# AUX_Sensor_Board.net
KiCad netlist of a schematic drawn in Altium Designer
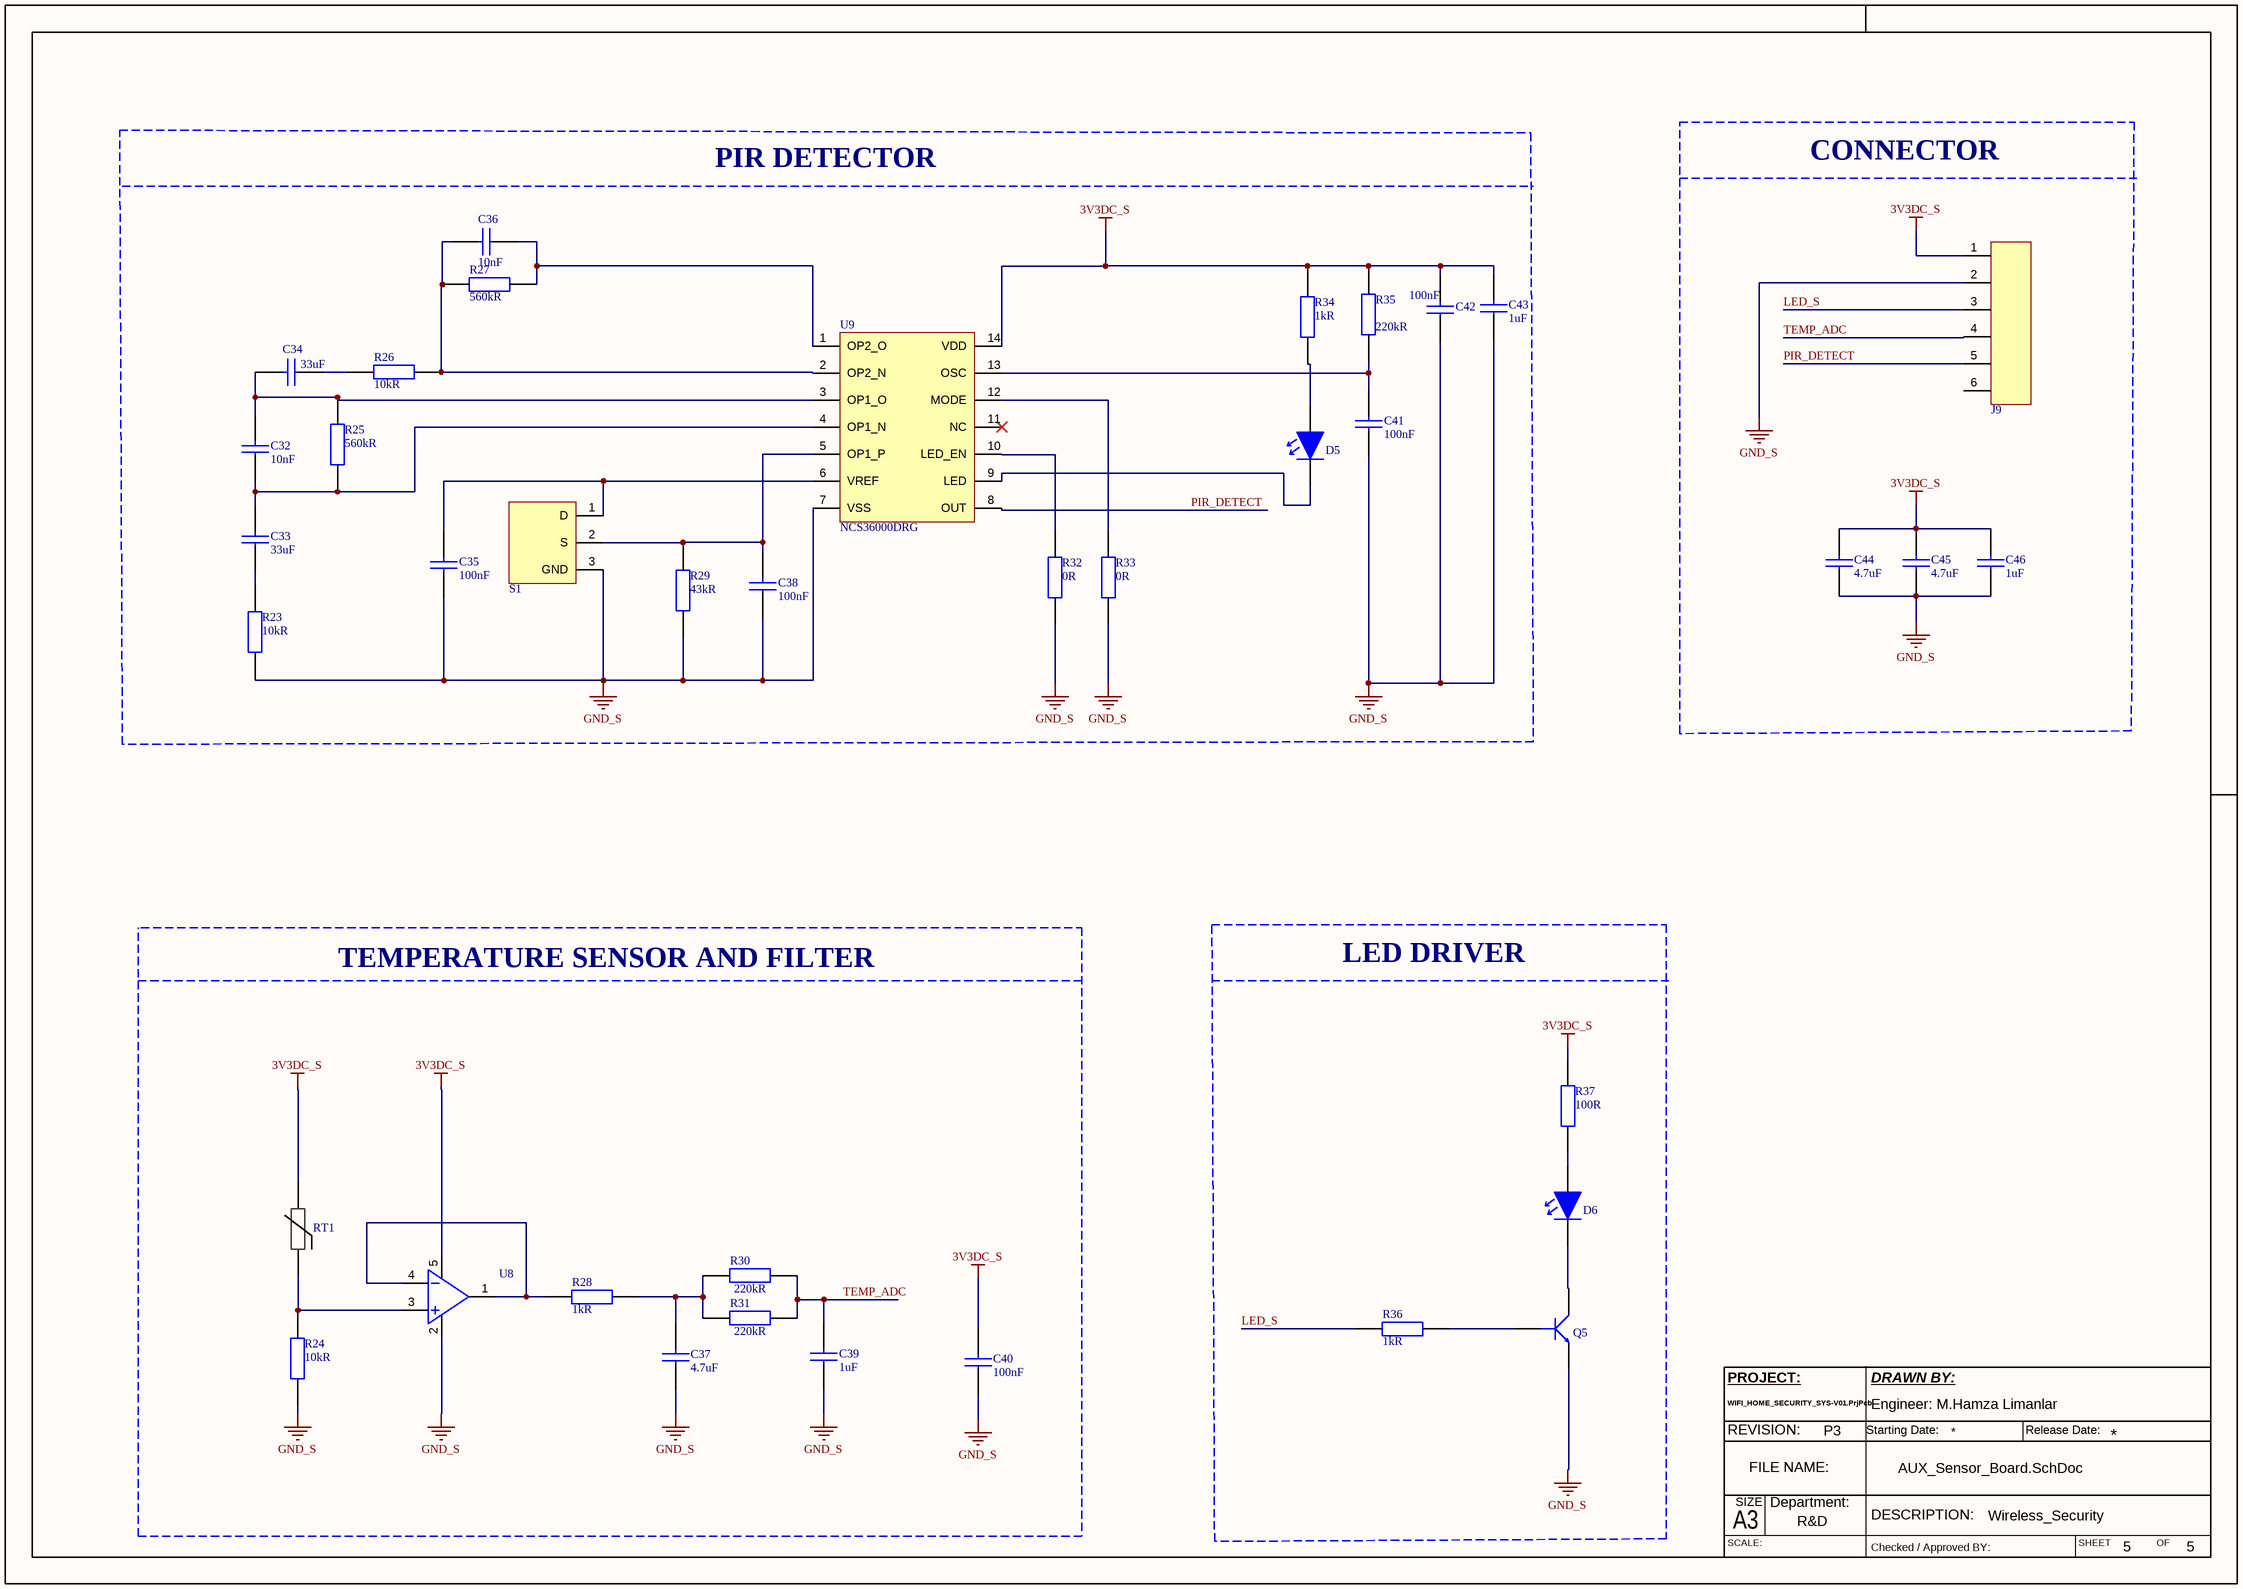
[diagram p0: AUX_Sensor_Board.SchDoc]

(export (version "E")
  (design (tool "Eeschema 10.0.6"))
  (components
    (comp (ref "C32")
      (value "0603B103K160CT")
      (footprint "CAP_0603")
      (description "CAP CER 10nF %10 0603")
      (fields
        (field (name "MANUFACTURER") "Walsin Technologies")
        (field (name "TOLERANCE") "10%")
        (field (name "CAPACITANCE") "10nF")
        (field (name "DESIGNED BY") "M.HamzaLimanlar")
      )
      (libsource (lib "HOME_SECURITY_SYSTEM_PROJECT_LIB") (part "CAP CER 10nF 0603"))
    )
    (comp (ref "C33")
      (value "C3216X5R1E336M160AC")
      (footprint "CAP_1206")
      (description "CAP CER 33uF %20 1206 SMD")
      (fields
        (field (name "MANUFACTURER") "TDK")
        (field (name "TOLERANCE") "20%")
        (field (name "CAPACITANCE") "33uF")
        (field (name "DESIGNED BY") "M.HamzaLimanlar")
      )
      (libsource (lib "HOME_SECURITY_SYSTEM_PROJECT_LIB") (part "CAP CER 33uF 1206"))
    )
    (comp (ref "C34")
      (value "C3216X5R1E336M160AC")
      (footprint "CAP_1206")
      (description "CAP CER 33uF %20 1206 SMD")
      (fields
        (field (name "MANUFACTURER") "TDK")
        (field (name "TOLERANCE") "20%")
        (field (name "CAPACITANCE") "33uF")
        (field (name "DESIGNED BY") "M.HamzaLimanlar")
      )
      (libsource (lib "HOME_SECURITY_SYSTEM_PROJECT_LIB") (part "CAP CER 33uF 1206"))
    )
    (comp (ref "C35")
      (value "C0603C104K5RACTU")
      (footprint "CAP_0603")
      (description "CAP CER 100nF %10 0603 SMD")
      (fields
        (field (name "MANUFACTURER") "KEMET")
        (field (name "TOLERANCE") "10%")
        (field (name "CAPACITANCE") "100nF")
        (field (name "DESIGNED BY") "M.HamzaLimanlar")
      )
      (libsource (lib "HOME_SECURITY_SYSTEM_PROJECT_LIB") (part "CAP CER 100nF 0603"))
    )
    (comp (ref "C36")
      (value "0603B103K160CT")
      (footprint "CAP_0603")
      (description "CAP CER 10nF %10 0603")
      (fields
        (field (name "MANUFACTURER") "Walsin Technologies")
        (field (name "TOLERANCE") "10%")
        (field (name "CAPACITANCE") "10nF")
        (field (name "DESIGNED BY") "M.HamzaLimanlar")
      )
      (libsource (lib "HOME_SECURITY_SYSTEM_PROJECT_LIB") (part "CAP CER 10nF 0603"))
    )
    (comp (ref "C37")
      (value "CL21A475KAQNNNE")
      (footprint "CAP_0805")
      (description "CAP CER 4.7uF %10 0805")
      (fields
        (field (name "MANUFACTURER") "Samsung")
        (field (name "TOLERANCE") "10%")
        (field (name "CAPACITANCE") "4.7uF")
        (field (name "DESIGNED BY") "M.HamzaLimanlar")
      )
      (libsource (lib "HOME_SECURITY_SYSTEM_PROJECT_LIB") (part "CAP CER 4.7uF 0805"))
    )
    (comp (ref "C38")
      (value "C0603C104K5RACTU")
      (footprint "CAP_0603")
      (description "CAP CER 100nF %10 0603 SMD")
      (fields
        (field (name "MANUFACTURER") "KEMET")
        (field (name "TOLERANCE") "10%")
        (field (name "CAPACITANCE") "100nF")
        (field (name "DESIGNED BY") "M.HamzaLimanlar")
      )
      (libsource (lib "HOME_SECURITY_SYSTEM_PROJECT_LIB") (part "CAP CER 100nF 0603"))
    )
    (comp (ref "C39")
      (value "CL21B105KBFNNNE")
      (footprint "CAP_0805")
      (description "CAP CER 1uF %10 0805")
      (fields
        (field (name "MANUFACTURER") "Samsung")
        (field (name "TOLERANCE") "10%")
        (field (name "CAPACITANCE") "1uF")
        (field (name "DESIGNED BY") "M.HamzaLimanlar")
      )
      (libsource (lib "HOME_SECURITY_SYSTEM_PROJECT_LIB") (part "CAP CER 1uF 0805"))
    )
    (comp (ref "C40")
      (value "C0603C104K5RACTU")
      (footprint "CAP_0603")
      (description "CAP CER 100nF %10 0603 SMD")
      (fields
        (field (name "MANUFACTURER") "KEMET")
        (field (name "TOLERANCE") "10%")
        (field (name "CAPACITANCE") "100nF")
        (field (name "DESIGNED BY") "M.HamzaLimanlar")
      )
      (libsource (lib "HOME_SECURITY_SYSTEM_PROJECT_LIB") (part "CAP CER 100nF 0603"))
    )
    (comp (ref "C41")
      (value "C0603C104K5RACTU")
      (footprint "CAP_0603")
      (description "CAP CER 100nF %10 0603 SMD")
      (fields
        (field (name "MANUFACTURER") "KEMET")
        (field (name "TOLERANCE") "10%")
        (field (name "CAPACITANCE") "100nF")
        (field (name "DESIGNED BY") "M.HamzaLimanlar")
      )
      (libsource (lib "HOME_SECURITY_SYSTEM_PROJECT_LIB") (part "CAP CER 100nF 0603"))
    )
    (comp (ref "C42")
      (value "C0603C104K5RACTU")
      (footprint "CAP_0603")
      (description "CAP CER 100nF %10 0603 SMD")
      (fields
        (field (name "MANUFACTURER") "KEMET")
        (field (name "TOLERANCE") "10%")
        (field (name "CAPACITANCE") "100nF")
        (field (name "DESIGNED BY") "M.HamzaLimanlar")
      )
      (libsource (lib "HOME_SECURITY_SYSTEM_PROJECT_LIB") (part "CAP CER 100nF 0603"))
    )
    (comp (ref "C43")
      (value "CL21B105KBFNNNE")
      (footprint "CAP_0805")
      (description "CAP CER 1uF %10 0805")
      (fields
        (field (name "MANUFACTURER") "Samsung")
        (field (name "TOLERANCE") "10%")
        (field (name "CAPACITANCE") "1uF")
        (field (name "DESIGNED BY") "M.HamzaLimanlar")
      )
      (libsource (lib "HOME_SECURITY_SYSTEM_PROJECT_LIB") (part "CAP CER 1uF 0805"))
    )
    (comp (ref "C44")
      (value "CL21A475KAQNNNE")
      (footprint "CAP_0805")
      (description "CAP CER 4.7uF %10 0805")
      (fields
        (field (name "MANUFACTURER") "Samsung")
        (field (name "TOLERANCE") "10%")
        (field (name "CAPACITANCE") "4.7uF")
        (field (name "DESIGNED BY") "M.HamzaLimanlar")
      )
      (libsource (lib "HOME_SECURITY_SYSTEM_PROJECT_LIB") (part "CAP CER 4.7uF 0805"))
    )
    (comp (ref "C45")
      (value "CL21A475KAQNNNE")
      (footprint "CAP_0805")
      (description "CAP CER 4.7uF %10 0805")
      (fields
        (field (name "MANUFACTURER") "Samsung")
        (field (name "TOLERANCE") "10%")
        (field (name "CAPACITANCE") "4.7uF")
        (field (name "DESIGNED BY") "M.HamzaLimanlar")
      )
      (libsource (lib "HOME_SECURITY_SYSTEM_PROJECT_LIB") (part "CAP CER 4.7uF 0805"))
    )
    (comp (ref "C46")
      (value "CL21B105KBFNNNE")
      (footprint "CAP_0805")
      (description "CAP CER 1uF %10 0805")
      (fields
        (field (name "MANUFACTURER") "Samsung")
        (field (name "TOLERANCE") "10%")
        (field (name "CAPACITANCE") "1uF")
        (field (name "DESIGNED BY") "M.HamzaLimanlar")
      )
      (libsource (lib "HOME_SECURITY_SYSTEM_PROJECT_LIB") (part "CAP CER 1uF 0805"))
    )
    (comp (ref "D5")
      (value "LTST-C171GKT")
      (footprint "LED_GREEN_0805")
      (description "Green 0805 130 º Min 5 mcd Typical 12 mcd Water Clear Lens SMT LED")
      (fields (field (name "MANUFACTURER") "Vishay Lite-On") (field (name "DESIGNED BY") "M.HamzaLimanlar"))
      (libsource (lib "HOME_SECURITY_SYSTEM_PROJECT_LIB") (part "LED GREEN 0805"))
    )
    (comp (ref "D6")
      (value "LH R974-LP-1")
      (footprint "LED_RED_0805")
      (description "LED Uni-Color Hyper Red 660nm 2-Pin Chip 0805(2012Metric) T/R")
      (fields (field (name "MANUFACTURER") "Osram Opto") (field (name "DESIGNED BY") "M.HamzaLimanlar"))
      (libsource (lib "HOME_SECURITY_SYSTEM_PROJECT_LIB") (part "LED RED 0805"))
    )
    (comp (ref "J9")
      (value "64800611622")
      (footprint "64800611622")
      (description "1.50mm 6PIN Connector")
      (fields
        (field (name "MANUFACTURER") "Wurth Electronics")
        (field (name "DESIGNED BY") "M.HamzaLimanlar")
      )
      (libsource (lib "HOME_SECURITY_SYSTEM_PROJECT_LIB") (part "64800611622_conn_6pin"))
    )
    (comp (ref "Q5")
      (value "MMBT3904-7-F")
      (footprint "SOT-23F")
      (description "Transistor General Purpose BJT NPN 40 Volt 0.2A Automotive 3-Pin SOT-23")
      (fields (field (name "MANUFACTURER") "Diodes Zetex") (field (name "DESIGNED BY") "M.HamzaLimanlar"))
      (libsource (lib "HOME_SECURITY_SYSTEM_PROJECT_LIB") (part "MMBT3904-7-F"))
    )
    (comp (ref "R23")
      (value "RC0603FR-0710KL")
      (footprint "RES_0603")
      (description "RES 10K %1 OHM 0603 SMD")
      (fields
        (field (name "MANUFACTURER") "Yageo")
        (field (name "TOLERANCE") "1%")
        (field (name "RESISTANCE") "10kR")
        (field (name "DESIGNED BY") "M.HamzaLimanlar")
      )
      (libsource (lib "HOME_SECURITY_SYSTEM_PROJECT_LIB") (part "RES 10K OHM 0603"))
    )
    (comp (ref "R24")
      (value "RC0603FR-0710KL")
      (footprint "RES_0603")
      (description "RES 10K %1 OHM 0603 SMD")
      (fields
        (field (name "MANUFACTURER") "Yageo")
        (field (name "TOLERANCE") "1%")
        (field (name "RESISTANCE") "10kR")
        (field (name "DESIGNED BY") "M.HamzaLimanlar")
      )
      (libsource (lib "HOME_SECURITY_SYSTEM_PROJECT_LIB") (part "RES 10K OHM 0603"))
    )
    (comp (ref "R25")
      (value "RC0603JR-07560KL")
      (footprint "RES_0603")
      (description "RES SMD 560K OHM 5% 1/10W 0603")
      (fields
        (field (name "MANUFACTURER") "Yageo")
        (field (name "TOLERANCE") "5%")
        (field (name "RESISTANCE") "560kR")
        (field (name "DESIGNED BY") "M.HamzaLimanlar")
      )
      (libsource (lib "") (part "RES 560K OHM 0603_1"))
    )
    (comp (ref "R26")
      (value "RC0603FR-0710KL")
      (footprint "RES_0603")
      (description "RES 10K %1 OHM 0603 SMD")
      (fields
        (field (name "MANUFACTURER") "Yageo")
        (field (name "TOLERANCE") "1%")
        (field (name "RESISTANCE") "10kR")
        (field (name "DESIGNED BY") "M.HamzaLimanlar")
      )
      (libsource (lib "") (part "RES 10K OHM 0603_1"))
    )
    (comp (ref "R27")
      (value "RC0603JR-07560KL")
      (footprint "RES_0603")
      (description "RES SMD 560K OHM 5% 1/10W 0603")
      (fields
        (field (name "MANUFACTURER") "Yageo")
        (field (name "TOLERANCE") "5%")
        (field (name "RESISTANCE") "560kR")
        (field (name "DESIGNED BY") "M.HamzaLimanlar")
      )
      (libsource (lib "HOME_SECURITY_SYSTEM_PROJECT_LIB") (part "RES 560K OHM 0603"))
    )
    (comp (ref "R28")
      (value "RC0603FR-0710KL")
      (footprint "RES_0603")
      (description "RES 1K %1 OHM 0603 SMD")
      (fields
        (field (name "MANUFACTURER") "Yageo")
        (field (name "MANUFACTURER PART NUMBER") "RC0603JR-071KL")
        (field (name "RESISTANCE") "1kR")
        (field (name "DESIGNED BY") "M.HamzaLimanlar")
      )
      (libsource (lib "HOME_SECURITY_SYSTEM_PROJECT_LIB") (part "RES 1K OHM 0603"))
    )
    (comp (ref "R29")
      (value "RC0603JR-0743KL")
      (footprint "RES_0603")
      (description "RES 43K %5 OHM 0603 SMD")
      (fields
        (field (name "MANUFACTURER") "Yageo")
        (field (name "TOLERANCE") "5%")
        (field (name "RESISTANCE") "43kR")
        (field (name "DESIGNED BY") "M.HamzaLimanlar")
      )
      (libsource (lib "HOME_SECURITY_SYSTEM_PROJECT_LIB") (part "RES 43K OHM 0603"))
    )
    (comp (ref "R30")
      (value "RC0603JR-07220KL")
      (footprint "RES_0603")
      (description "RES 220K %5 OHM 0603 SMD")
      (fields
        (field (name "MANUFACTURER") "Yageo")
        (field (name "TOLERANCE") "5%")
        (field (name "RESISTANCE") "220kR")
      )
      (libsource (lib "HOME_SECURITY_SYSTEM_PROJECT_LIB") (part "RES 220K OHM 0603"))
    )
    (comp (ref "R31")
      (value "RC0603JR-07220KL")
      (footprint "RES_0603")
      (description "RES 220K %5 OHM 0603 SMD")
      (fields
        (field (name "MANUFACTURER") "Yageo")
        (field (name "TOLERANCE") "5%")
        (field (name "RESISTANCE") "220kR")
      )
      (libsource (lib "HOME_SECURITY_SYSTEM_PROJECT_LIB") (part "RES 220K OHM 0603"))
    )
    (comp (ref "R32")
      (value "RC0603JR-070RL")
      (footprint "RES_0603")
      (description "RES 0 %1 OHM 0603 SMD")
      (fields
        (field (name "MANUFACTURER") "Yageo")
        (field (name "TOLERANCE") "1%")
        (field (name "RESISTANCE") "0R")
        (field (name "DESIGNED BY") "M.HamzaLimanlar")
      )
      (libsource (lib "HOME_SECURITY_SYSTEM_PROJECT_LIB") (part "RES 0 OHM 0603"))
    )
    (comp (ref "R33")
      (value "RC0603JR-070RL")
      (footprint "RES_0603")
      (description "RES 0 %1 OHM 0603 SMD")
      (fields
        (field (name "MANUFACTURER") "Yageo")
        (field (name "TOLERANCE") "1%")
        (field (name "RESISTANCE") "0R")
        (field (name "DESIGNED BY") "M.HamzaLimanlar")
      )
      (libsource (lib "HOME_SECURITY_SYSTEM_PROJECT_LIB") (part "RES 0 OHM 0603"))
    )
    (comp (ref "R34")
      (value "RC0603FR-0710KL")
      (footprint "RES_0603")
      (description "RES 1K %1 OHM 0603 SMD")
      (fields
        (field (name "MANUFACTURER") "Yageo")
        (field (name "MANUFACTURER PART NUMBER") "RC0603JR-071KL")
        (field (name "RESISTANCE") "1kR")
        (field (name "DESIGNED BY") "M.HamzaLimanlar")
      )
      (libsource (lib "") (part "RES 1K OHM 0603_1"))
    )
    (comp (ref "R35")
      (value "RC0603JR-07220KL")
      (footprint "RES_0603")
      (description "RES 220K %5 OHM 0603 SMD")
      (fields
        (field (name "MANUFACTURER") "Yageo")
        (field (name "TOLERANCE") "5%")
        (field (name "RESISTANCE") "220kR")
      )
      (libsource (lib "") (part "RES 220K OHM 0603_1"))
    )
    (comp (ref "R36")
      (value "RC0603FR-0710KL")
      (footprint "RES_0603")
      (description "RES 1K %1 OHM 0603 SMD")
      (fields
        (field (name "MANUFACTURER") "Yageo")
        (field (name "MANUFACTURER PART NUMBER") "RC0603JR-071KL")
        (field (name "RESISTANCE") "1kR")
        (field (name "DESIGNED BY") "M.HamzaLimanlar")
      )
      (libsource (lib "HOME_SECURITY_SYSTEM_PROJECT_LIB") (part "RES 1K OHM 0603"))
    )
    (comp (ref "R37")
      (value "RC0603JR-07100RL")
      (footprint "RES_0603")
      (description "RES 100 %5 OHM 0603 SMD")
      (fields
        (field (name "MANUFACTURER") "Yageo")
        (field (name "TOLERANCE") "5%")
        (field (name "RESISTANCE") "100R")
        (field (name "DESIGNED BY") "M.HamzaLimanlar")
      )
      (libsource (lib "HOME_SECURITY_SYSTEM_PROJECT_LIB") (part "RES 100 OHM 0603"))
    )
    (comp (ref "RT1")
      (value "TFPT1206L1002FM")
      (footprint "RES_1206")
      (description "Thermistor PTC 10K Ohm 1% 1206")
      (fields
        (field (name "MANUFACTURER") "Vishay Dale")
        (field (name "TOLERANCE") "1%")
        (field (name "DESIGNED BY") "M.HamzaLimanlar")
      )
      (libsource (lib "HOME_SECURITY_SYSTEM_PROJECT_LIB") (part "TFPT1206L1002FM"))
    )
    (comp (ref "S1")
      (value "LHI 878/3902")
      (footprint "LHI 878")
      (description "SENSOR PYRO DETECTOR DUAL MOTION")
      (fields (field (name "DESIGNED BY") "M.HamzaLimanlar"))
      (libsource (lib "HOME_SECURITY_SYSTEM_PROJECT_LIB") (part "LHI 878/3902"))
    )
    (comp (ref "U8")
      (value "OPA314AIDBVR")
      (footprint "SOT23-5")
      (description "Op Amp OPA314")
      (fields
        (field (name "MANUFACTURER") "Texas Instruments")
        (field (name "DESIGNED BY") "M.HamzaLimanlar")
      )
      (libsource (lib "HOME_SECURITY_SYSTEM_PROJECT_LIB") (part "OPA314"))
    )
    (comp (ref "U9")
      (value "NCS36000DRG")
      (footprint "SOIC14")
      (description "PIR Controller Low Noise Amplifiers and LDO Regulator 14-Pin SOIC N T/R")
      (fields (field (name "MANUFACTURER") "ON Semiconductor") (field (name "DESIGNED BY") "M.HamzaLimanlar"))
      (libsource (lib "HOME_SECURITY_SYSTEM_PROJECT_LIB") (part "NCS36000"))
    )
  )
  (nets
    (net (code "1") (name "/LED_S") (class "Default")
      (node (ref "J9") (pin "3") (pintype "power_in"))
      (node (ref "R36") (pin "1") (pinfunction "1_1") (pintype "passive"))
    )
    (net (code "2") (name "/PIR_DETECT") (class "Default")
      (node (ref "J9") (pin "5") (pintype "power_in"))
      (node (ref "U9") (pin "8") (pinfunction "OUT_8") (pintype "passive"))
    )
    (net (code "3") (name "/TEMP_ADC") (class "Default")
      (node (ref "C39") (pin "2") (pinfunction "2_2") (pintype "passive"))
      (node (ref "J9") (pin "4") (pintype "power_in"))
      (node (ref "R30") (pin "2") (pinfunction "2_2") (pintype "passive"))
      (node (ref "R31") (pin "2") (pinfunction "2_2") (pintype "passive"))
    )
    (net (code "4") (name "3V3DC_S") (class "Default")
      (node (ref "C40") (pin "2") (pinfunction "2_2") (pintype "passive"))
      (node (ref "C42") (pin "2") (pinfunction "2_2") (pintype "passive"))
      (node (ref "C43") (pin "2") (pinfunction "2_2") (pintype "passive"))
      (node (ref "C44") (pin "2") (pinfunction "2_2") (pintype "passive"))
      (node (ref "C45") (pin "2") (pinfunction "2_2") (pintype "passive"))
      (node (ref "C46") (pin "2") (pinfunction "2_2") (pintype "passive"))
      (node (ref "J9") (pin "1") (pintype "power_in"))
      (node (ref "R34") (pin "2") (pinfunction "2_2") (pintype "passive"))
      (node (ref "R35") (pin "2") (pinfunction "2_2") (pintype "passive"))
      (node (ref "R37") (pin "2") (pinfunction "2_2") (pintype "passive"))
      (node (ref "RT1") (pin "2") (pinfunction "2_2") (pintype "passive"))
      (node (ref "U8") (pin "5") (pinfunction "5_5") (pintype "passive"))
      (node (ref "U9") (pin "14") (pinfunction "VDD_14") (pintype "passive"))
    )
    (net (code "5") (name "GND_S") (class "Default")
      (node (ref "C35") (pin "1") (pinfunction "1_1") (pintype "passive"))
      (node (ref "C37") (pin "1") (pinfunction "1_1") (pintype "passive"))
      (node (ref "C38") (pin "1") (pinfunction "1_1") (pintype "passive"))
      (node (ref "C39") (pin "1") (pinfunction "1_1") (pintype "passive"))
      (node (ref "C40") (pin "1") (pinfunction "1_1") (pintype "passive"))
      (node (ref "C41") (pin "1") (pinfunction "1_1") (pintype "passive"))
      (node (ref "C42") (pin "1") (pinfunction "1_1") (pintype "passive"))
      (node (ref "C43") (pin "1") (pinfunction "1_1") (pintype "passive"))
      (node (ref "C44") (pin "1") (pinfunction "1_1") (pintype "passive"))
      (node (ref "C45") (pin "1") (pinfunction "1_1") (pintype "passive"))
      (node (ref "C46") (pin "1") (pinfunction "1_1") (pintype "passive"))
      (node (ref "J9") (pin "2") (pintype "power_in"))
      (node (ref "Q5") (pin "2") (pinfunction "E_2") (pintype "power_in"))
      (node (ref "R23") (pin "1") (pinfunction "1_1") (pintype "passive"))
      (node (ref "R24") (pin "1") (pinfunction "1_1") (pintype "passive"))
      (node (ref "R29") (pin "1") (pinfunction "1_1") (pintype "passive"))
      (node (ref "R32") (pin "1") (pinfunction "1_1") (pintype "passive"))
      (node (ref "R33") (pin "1") (pinfunction "1_1") (pintype "passive"))
      (node (ref "S1") (pin "3") (pinfunction "GND_3") (pintype "passive"))
      (node (ref "U8") (pin "2") (pinfunction "2_2") (pintype "passive"))
      (node (ref "U9") (pin "7") (pinfunction "VSS_7") (pintype "passive"))
    )
    (net (code "6") (name "Net-(C33-Pad1)") (class "Default")
      (node (ref "C33") (pin "1") (pinfunction "1_1") (pintype "passive"))
      (node (ref "R23") (pin "2") (pinfunction "2_2") (pintype "passive"))
    )
    (net (code "7") (name "Net-(C34-Pad1)") (class "Default")
      (node (ref "C34") (pin "1") (pinfunction "1_1") (pintype "passive"))
      (node (ref "R26") (pin "2") (pinfunction "2_2") (pintype "passive"))
    )
    (net (code "8") (name "Net-(C37-Pad2)") (class "Default")
      (node (ref "C37") (pin "2") (pinfunction "2_2") (pintype "passive"))
      (node (ref "R28") (pin "2") (pinfunction "2_2") (pintype "passive"))
      (node (ref "R30") (pin "1") (pinfunction "1_1") (pintype "passive"))
      (node (ref "R31") (pin "1") (pinfunction "1_1") (pintype "passive"))
    )
    (net (code "9") (name "Net-(D5-Pad2)") (class "Default")
      (node (ref "D5") (pin "2") (pinfunction "2_2") (pintype "power_in"))
      (node (ref "R34") (pin "1") (pinfunction "1_1") (pintype "passive"))
    )
    (net (code "10") (name "Net-(D6-Pad2)") (class "Default")
      (node (ref "D6") (pin "2") (pinfunction "2_2") (pintype "power_in"))
      (node (ref "R37") (pin "1") (pinfunction "1_1") (pintype "passive"))
    )
    (net (code "11") (name "Net-(Q5-B)") (class "Default")
      (node (ref "Q5") (pin "1") (pinfunction "B_1") (pintype "power_in"))
      (node (ref "R36") (pin "2") (pinfunction "2_2") (pintype "passive"))
    )
    (net (code "12") (name "Net-(Q5-C)") (class "Default")
      (node (ref "D6") (pin "1") (pinfunction "1_1") (pintype "power_in"))
      (node (ref "Q5") (pin "3") (pinfunction "C_3") (pintype "power_in"))
    )
    (net (code "13") (name "Net-(R24-Pad2)") (class "Default")
      (node (ref "R24") (pin "2") (pinfunction "2_2") (pintype "passive"))
      (node (ref "RT1") (pin "1") (pinfunction "1_1") (pintype "passive"))
      (node (ref "U8") (pin "3") (pinfunction "3_3") (pintype "passive"))
    )
    (net (code "14") (name "Net-(R28-Pad1)") (class "Default")
      (node (ref "R28") (pin "1") (pinfunction "1_1") (pintype "passive"))
      (node (ref "U8") (pin "1") (pinfunction "1_1") (pintype "passive"))
      (node (ref "U8") (pin "4") (pinfunction "4_4") (pintype "passive"))
    )
    (net (code "15") (name "Net-(S1-D)") (class "Default")
      (node (ref "C35") (pin "2") (pinfunction "2_2") (pintype "passive"))
      (node (ref "S1") (pin "1") (pinfunction "D_1") (pintype "passive"))
      (node (ref "U9") (pin "6") (pinfunction "VREF_6") (pintype "passive"))
    )
    (net (code "16") (name "Net-(S1-S)") (class "Default")
      (node (ref "C38") (pin "2") (pinfunction "2_2") (pintype "passive"))
      (node (ref "R29") (pin "2") (pinfunction "2_2") (pintype "passive"))
      (node (ref "S1") (pin "2") (pinfunction "S_2") (pintype "passive"))
      (node (ref "U9") (pin "5") (pinfunction "OP1_P_5") (pintype "passive"))
    )
    (net (code "17") (name "Net-(U9-LED)") (class "Default")
      (node (ref "D5") (pin "1") (pinfunction "1_1") (pintype "power_in"))
      (node (ref "U9") (pin "9") (pinfunction "LED_9") (pintype "passive"))
    )
    (net (code "18") (name "Net-(U9-LED_EN)") (class "Default")
      (node (ref "R32") (pin "2") (pinfunction "2_2") (pintype "passive"))
      (node (ref "U9") (pin "10") (pinfunction "LED_EN_10") (pintype "passive"))
    )
    (net (code "19") (name "Net-(U9-MODE)") (class "Default")
      (node (ref "R33") (pin "2") (pinfunction "2_2") (pintype "passive"))
      (node (ref "U9") (pin "12") (pinfunction "MODE_12") (pintype "passive"))
    )
    (net (code "20") (name "Net-(U9-OP1_N)") (class "Default")
      (node (ref "C32") (pin "1") (pinfunction "1_1") (pintype "passive"))
      (node (ref "C33") (pin "2") (pinfunction "2_2") (pintype "passive"))
      (node (ref "R25") (pin "1") (pinfunction "1_1") (pintype "passive"))
      (node (ref "U9") (pin "4") (pinfunction "OP1_N_4") (pintype "passive"))
    )
    (net (code "21") (name "Net-(U9-OP1_O)") (class "Default")
      (node (ref "C32") (pin "2") (pinfunction "2_2") (pintype "passive"))
      (node (ref "C34") (pin "2") (pinfunction "2_2") (pintype "passive"))
      (node (ref "R25") (pin "2") (pinfunction "2_2") (pintype "passive"))
      (node (ref "U9") (pin "3") (pinfunction "OP1_O_3") (pintype "passive"))
    )
    (net (code "22") (name "Net-(U9-OP2_N)") (class "Default")
      (node (ref "C36") (pin "2") (pinfunction "2_2") (pintype "passive"))
      (node (ref "R26") (pin "1") (pinfunction "1_1") (pintype "passive"))
      (node (ref "R27") (pin "2") (pinfunction "2_2") (pintype "passive"))
      (node (ref "U9") (pin "2") (pinfunction "OP2_N_2") (pintype "passive"))
    )
    (net (code "23") (name "Net-(U9-OP2_O)") (class "Default")
      (node (ref "C36") (pin "1") (pinfunction "1_1") (pintype "passive"))
      (node (ref "R27") (pin "1") (pinfunction "1_1") (pintype "passive"))
      (node (ref "U9") (pin "1") (pinfunction "OP2_O_1") (pintype "passive"))
    )
    (net (code "24") (name "Net-(U9-OSC)") (class "Default")
      (node (ref "C41") (pin "2") (pinfunction "2_2") (pintype "passive"))
      (node (ref "R35") (pin "1") (pinfunction "1_1") (pintype "passive"))
      (node (ref "U9") (pin "13") (pinfunction "OSC_13") (pintype "passive"))
    )
    (net (code "25") (name "unconnected-(J9-Pad6)") (class "Default")
      (node (ref "J9") (pin "6") (pintype "power_in"))
    )
    (net (code "26") (name "unconnected-(U9-NC-Pad11)") (class "Default")
      (node (ref "U9") (pin "11") (pinfunction "NC_11") (pintype "passive+no_connect"))
    )
  )
)
